# SunS_fixture_EGSE_LDO.net
KiCad netlist of a schematic drawn in Altium Designer
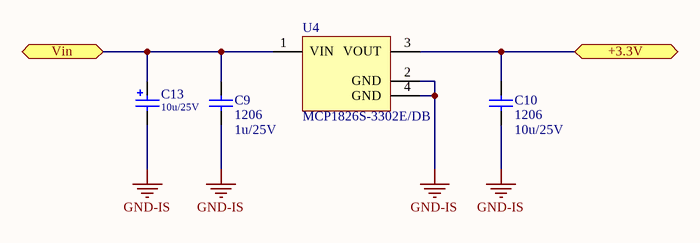
[diagram p0: SunS_fixture_EGSE_LDO.SchDoc]

(export (version "E")
  (design (tool "Eeschema 10.0.6"))
  (components
    (comp (ref "C9")
      (value "1u/25V")
      (footprint "SMD_Capacitor_1206")
      (description "Ceramic Cap Kemet COTS 1u/25V X7R 1206")
      (fields
        (field (name "MANUFACTURERPARTNUMBER") "C1206T105K3RALTU")
        (field (name "MANUFACTURER") "Kemet")
        (field (name "PACKAGE") "1206")
      )
      (libsource (lib "capacitors") (part "Cer_C1206T105K3RALTU"))
    )
    (comp (ref "C10")
      (value "10u/25V")
      (footprint "SMD_Capacitor_1206")
      (description "Ceramic Cap Kemet COTS 1u/25V X7R 1206")
      (fields
        (field (name "MANUFACTURERPARTNUMBER") "C1206T105K3RALTU")
        (field (name "MANUFACTURER") "Kemet")
        (field (name "PACKAGE") "1206")
      )
      (libsource (lib "capacitors") (part "Cer_C1206T105K3RALTU"))
    )
    (comp (ref "C13")
      (value "10u/25V")
      (footprint "Tantalum_cap_D")
      (description "Tantalum Capacitor CWR11 10u/22V.")
      (fields
        (field (name "MANUFACTURERPARTNUMBER") "CWR11K(6)106(1)(2)(5)")
        (field (name "MANUFACTURER") "Kemet")
      )
      (libsource (lib "capacitors") (part "TantS_CWR11_10u_25V"))
    )
    (comp (ref "U4")
      (value "MCP1826S-3302E/DB")
      (footprint "SOT-223-DB3_M")
      (description "1000 mA, Low Voltage, Low Quiescent Current LDO Regulator, 3-Pin SOT-223, Extended Temperature")
      (fields (field (name "MANUFACTURER") "Microchip"))
      (libsource (lib "microcircuits") (part "MCP1826S-3302E/DB"))
    )
  )
  (nets
    (net (code "1") (name "/+3.3V") (class "Default")
      (node (ref "C10") (pin "1") (pinfunction "1_1") (pintype "passive"))
      (node (ref "U4") (pin "3") (pinfunction "VOUT_3") (pintype "power_in"))
    )
    (net (code "2") (name "/Vin") (class "Default")
      (node (ref "C13") (pin "1") (pinfunction "1_1") (pintype "passive"))
      (node (ref "C9") (pin "1") (pinfunction "1_1") (pintype "passive"))
      (node (ref "U4") (pin "1") (pinfunction "VIN_1") (pintype "power_in"))
    )
    (net (code "3") (name "GND-IS") (class "Default")
      (node (ref "C10") (pin "2") (pinfunction "2_2") (pintype "passive"))
      (node (ref "C13") (pin "2") (pinfunction "2_2") (pintype "passive"))
      (node (ref "C9") (pin "2") (pinfunction "2_2") (pintype "passive"))
      (node (ref "U4") (pin "2") (pinfunction "GND_2") (pintype "power_in"))
      (node (ref "U4") (pin "4") (pinfunction "GND_4") (pintype "power_in"))
    )
  )
)
